# M_Driver.net
KiCad netlist of a schematic drawn in Altium Designer
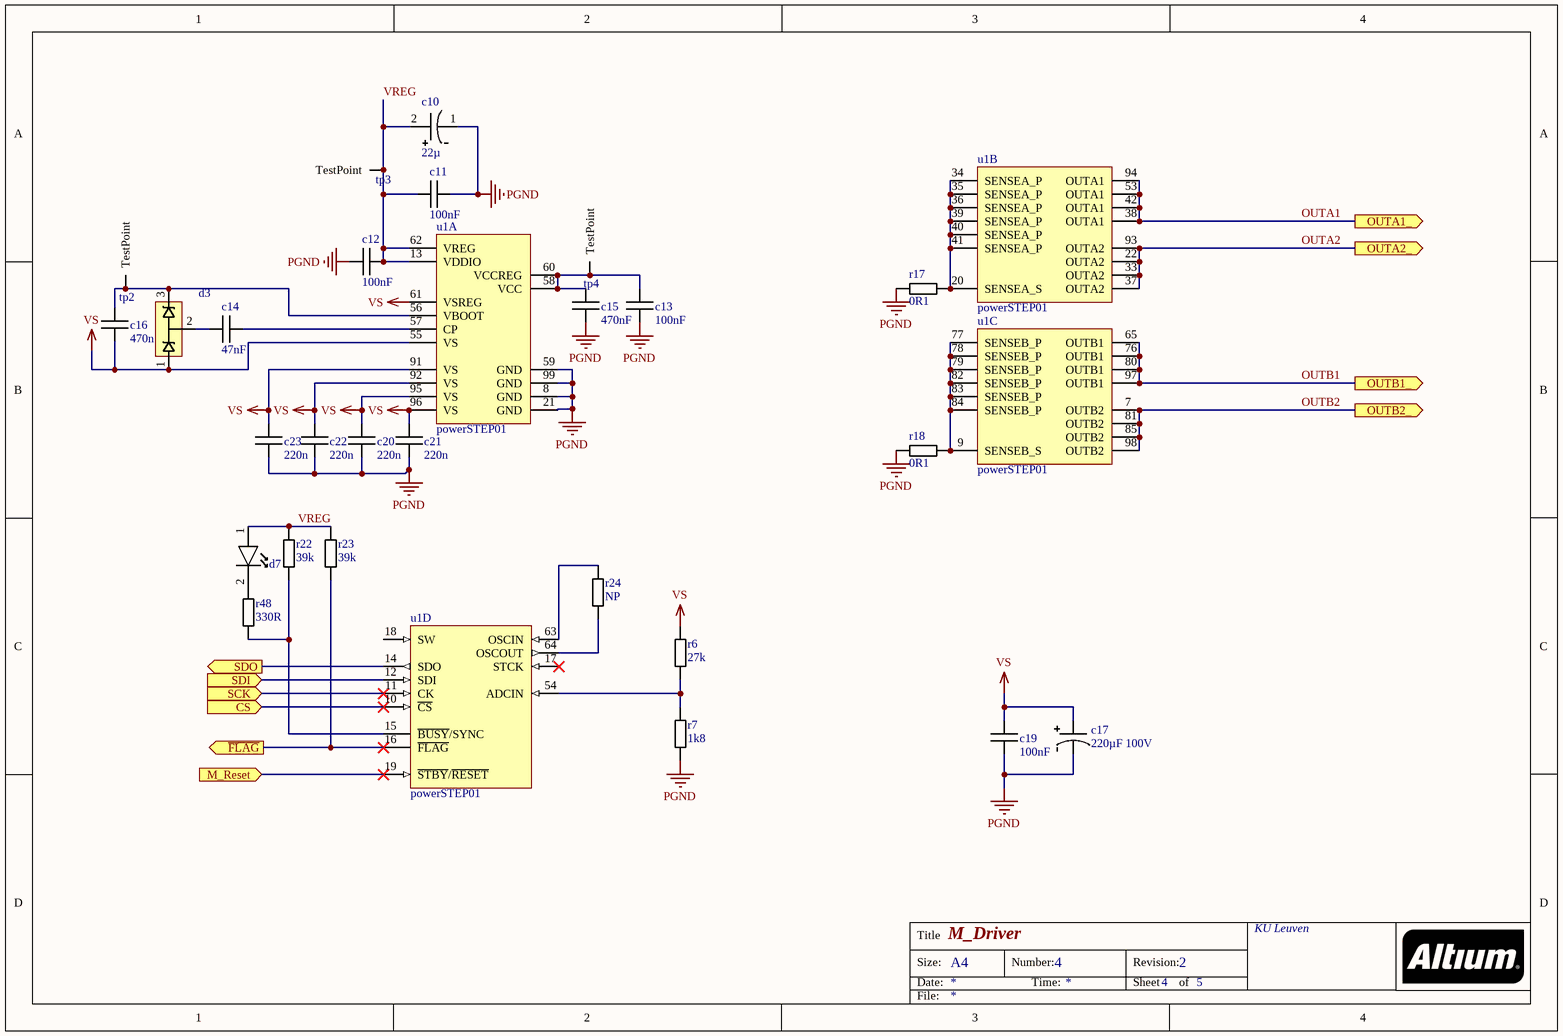
[diagram p0: M_Driver.SchDoc]

(export (version "E")
  (design (tool "Eeschema 10.0.6"))
  (components
    (comp (ref "c10") (value "22µ") (footprint "Elco-B") (libsource (lib "Panasonic") (part "Elco B")))
    (comp (ref "c11")
      (value "100nF")
      (footprint "0805")
      (description "...F")
      (libsource (lib "Generic R-C") (part "0805 Capacitor"))
    )
    (comp (ref "c12")
      (value "100nF")
      (footprint "0805")
      (description "...F")
      (libsource (lib "Generic R-C") (part "0805 Capacitor"))
    )
    (comp (ref "c13")
      (value "100nF")
      (footprint "0805")
      (description "...F")
      (libsource (lib "Generic R-C") (part "0805 Capacitor"))
    )
    (comp (ref "c14")
      (value "47nF")
      (footprint "0805")
      (description "...F")
      (libsource (lib "Generic R-C") (part "0805 Capacitor"))
    )
    (comp (ref "c15")
      (value "470nF")
      (footprint "0805")
      (description "...F")
      (libsource (lib "Generic R-C") (part "0805 Capacitor"))
    )
    (comp (ref "c16")
      (value "470n")
      (footprint "0805")
      (description "...F")
      (libsource (lib "Generic R-C") (part "0805 Capacitor"))
    )
    (comp (ref "c17")
      (value "220µF 100V")
      (footprint "TH Elco 12.5")
      (description "d = 12.5mm")
      (libsource (lib "Panasonic") (part "Elco TH d12.5"))
    )
    (comp (ref "c19")
      (value "100nF")
      (footprint "0805")
      (description "...F")
      (libsource (lib "Generic R-C") (part "0805 Capacitor"))
    )
    (comp (ref "c20")
      (value "220n")
      (footprint "0805")
      (description "...F")
      (libsource (lib "Generic R-C") (part "0805 Capacitor"))
    )
    (comp (ref "c21")
      (value "220n")
      (footprint "0805")
      (description "...F")
      (libsource (lib "Generic R-C") (part "0805 Capacitor"))
    )
    (comp (ref "c22")
      (value "220n")
      (footprint "0805")
      (description "...F")
      (libsource (lib "Generic R-C") (part "0805 Capacitor"))
    )
    (comp (ref "c23")
      (value "220n")
      (footprint "0805")
      (description "...F")
      (libsource (lib "Generic R-C") (part "0805 Capacitor"))
    )
    (comp (ref "d3") (value "BAS40-04") (footprint "SOT23") (libsource (lib "Diodes_inc") (part "BAS40-04")))
    (comp (ref "d7")
      (value "Yellow SMD LED")
      (footprint "0603 - LED")
      (description "0603 Package")
      (libsource (lib "Kingbright") (part "Yellow SMD LED"))
    )
    (comp (ref "r6")
      (value "27k")
      (footprint "0805")
      (description "...R")
      (libsource (lib "Generic R-C") (part "0805 Resistor"))
    )
    (comp (ref "r7")
      (value "1k8")
      (footprint "0805")
      (description "...R")
      (libsource (lib "Generic R-C") (part "0805 Resistor"))
    )
    (comp (ref "r17")
      (value "0R1")
      (footprint "2512")
      (description "..R")
      (libsource (lib "Generic R-C") (part "2512 Resistor"))
    )
    (comp (ref "r18")
      (value "0R1")
      (footprint "2512")
      (description "..R")
      (libsource (lib "Generic R-C") (part "2512 Resistor"))
    )
    (comp (ref "r22")
      (value "39k")
      (footprint "0805")
      (description "...R")
      (libsource (lib "Generic R-C") (part "0805 Resistor"))
    )
    (comp (ref "r23")
      (value "39k")
      (footprint "0805")
      (description "...R")
      (libsource (lib "Generic R-C") (part "0805 Resistor"))
    )
    (comp (ref "r24")
      (value "NP")
      (footprint "0603")
      (description "...R")
      (libsource (lib "Generic R-C") (part "0603 Resistor"))
    )
    (comp (ref "r48")
      (value "330R")
      (footprint "0603")
      (description "...R")
      (libsource (lib "Generic R-C") (part "0603 Resistor"))
    )
    (comp (ref "tp2")
      (value "Test Point")
      (footprint "Test Point")
      (libsource (lib "Board_Props") (part "Test Point"))
    )
    (comp (ref "tp3")
      (value "Test Point")
      (footprint "Test Point")
      (libsource (lib "Board_Props") (part "Test Point"))
    )
    (comp (ref "tp4")
      (value "Test Point")
      (footprint "Test Point")
      (libsource (lib "Board_Props") (part "Test Point"))
    )
    (comp (ref "u1")
      (value "powerSTEP01")
      (footprint "VFQFPN")
      (description "VFQFPN")
      (libsource (lib "STMicroelectronics") (part "powerSTEP01"))
    )
  )
  (nets
    (net (code "1") (name "/CS") (class "Default")
      (node (ref "u1") (pin "10") (pinfunction "~{CS}_10") (pintype "input+no_connect"))
    )
    (net (code "2") (name "/M_Reset") (class "Default")
      (node (ref "u1") (pin "19") (pinfunction "~{STBY}/~{RESET}_19") (pintype "input+no_connect"))
    )
    (net (code "3") (name "/OUTA1") (class "Default")
      (node (ref "u1") (pin "38") (pinfunction "OUTA1_38") (pintype "passive"))
      (node (ref "u1") (pin "42") (pinfunction "OUTA1_42") (pintype "passive"))
      (node (ref "u1") (pin "53") (pinfunction "OUTA1_53") (pintype "passive"))
      (node (ref "u1") (pin "94") (pinfunction "OUTA1_94") (pintype "passive"))
    )
    (net (code "4") (name "/OUTA2") (class "Default")
      (node (ref "u1") (pin "22") (pinfunction "OUTA2_22") (pintype "passive"))
      (node (ref "u1") (pin "33") (pinfunction "OUTA2_33") (pintype "passive"))
      (node (ref "u1") (pin "37") (pinfunction "OUTA2_37") (pintype "passive"))
      (node (ref "u1") (pin "93") (pinfunction "OUTA2_93") (pintype "passive"))
    )
    (net (code "5") (name "/OUTB1") (class "Default")
      (node (ref "u1") (pin "65") (pinfunction "OUTB1_65") (pintype "passive"))
      (node (ref "u1") (pin "76") (pinfunction "OUTB1_76") (pintype "passive"))
      (node (ref "u1") (pin "80") (pinfunction "OUTB1_80") (pintype "passive"))
      (node (ref "u1") (pin "97") (pinfunction "OUTB1_97") (pintype "passive"))
    )
    (net (code "6") (name "/OUTB2") (class "Default")
      (node (ref "u1") (pin "7") (pinfunction "OUTB2_7") (pintype "passive"))
      (node (ref "u1") (pin "81") (pinfunction "OUTB2_81") (pintype "passive"))
      (node (ref "u1") (pin "85") (pinfunction "OUTB2_85") (pintype "passive"))
      (node (ref "u1") (pin "98") (pinfunction "OUTB2_98") (pintype "passive"))
    )
    (net (code "7") (name "/SCK") (class "Default")
      (node (ref "u1") (pin "11") (pinfunction "CK_11") (pintype "input+no_connect"))
    )
    (net (code "8") (name "/SDI") (class "Default")
      (node (ref "u1") (pin "12") (pinfunction "SDI_12") (pintype "input"))
    )
    (net (code "9") (name "/SDO") (class "Default")
      (node (ref "u1") (pin "14") (pinfunction "SDO_14") (pintype "output"))
    )
    (net (code "10") (name "/VREG") (class "Default")
      (node (ref "c10") (pin "2") (pintype "passive"))
      (node (ref "c11") (pin "2") (pintype "passive"))
      (node (ref "c12") (pin "1") (pintype "passive"))
      (node (ref "d7") (pin "1") (pinfunction "Anode_1") (pintype "passive"))
      (node (ref "r22") (pin "1") (pintype "passive"))
      (node (ref "r23") (pin "1") (pintype "passive"))
      (node (ref "tp3") (pin "1") (pinfunction "TestPoint_1") (pintype "passive"))
      (node (ref "u1") (pin "13") (pinfunction "VDDIO_13") (pintype "power_in"))
      (node (ref "u1") (pin "62") (pinfunction "VREG_62") (pintype "power_in"))
    )
    (net (code "11") (name "/~{FLAG}") (class "Default")
      (node (ref "r23") (pin "2") (pintype "passive"))
      (node (ref "u1") (pin "16") (pinfunction "~{FLAG}_16") (pintype "open_collector"))
    )
    (net (code "12") (name "Net-(c14-Pad1)") (class "Default")
      (node (ref "c14") (pin "1") (pintype "passive"))
      (node (ref "d3") (pin "2") (pinfunction "2_2") (pintype "passive"))
    )
    (net (code "13") (name "Net-(d7-Kathode)") (class "Default")
      (node (ref "d7") (pin "2") (pinfunction "Kathode_2") (pintype "passive"))
      (node (ref "r48") (pin "2") (pintype "passive"))
    )
    (net (code "14") (name "Net-(tp2-TestPoint)") (class "Default")
      (node (ref "c16") (pin "1") (pintype "passive"))
      (node (ref "d3") (pin "3") (pinfunction "3_3") (pintype "passive"))
      (node (ref "tp2") (pin "1") (pinfunction "TestPoint_1") (pintype "passive"))
      (node (ref "u1") (pin "56") (pinfunction "VBOOT_56") (pintype "power_in"))
    )
    (net (code "15") (name "Net-(tp4-TestPoint)") (class "Default")
      (node (ref "c13") (pin "2") (pintype "passive"))
      (node (ref "c15") (pin "2") (pintype "passive"))
      (node (ref "tp4") (pin "1") (pinfunction "TestPoint_1") (pintype "passive"))
      (node (ref "u1") (pin "58") (pinfunction "VCC_58") (pintype "power_in"))
      (node (ref "u1") (pin "60") (pinfunction "VCCREG_60") (pintype "power_in"))
    )
    (net (code "16") (name "Net-(u1A-CP)") (class "Default")
      (node (ref "c14") (pin "2") (pintype "passive"))
      (node (ref "u1") (pin "57") (pinfunction "CP_57") (pintype "power_in"))
    )
    (net (code "17") (name "Net-(u1B-SENSEA_S)") (class "Default")
      (node (ref "r17") (pin "2") (pintype "passive"))
      (node (ref "u1") (pin "20") (pinfunction "SENSEA_S_20") (pintype "power_in"))
      (node (ref "u1") (pin "34") (pinfunction "SENSEA_P_34") (pintype "power_in"))
      (node (ref "u1") (pin "35") (pinfunction "SENSEA_P_35") (pintype "power_in"))
      (node (ref "u1") (pin "36") (pinfunction "SENSEA_P_36") (pintype "power_in"))
      (node (ref "u1") (pin "39") (pinfunction "SENSEA_P_39") (pintype "power_in"))
      (node (ref "u1") (pin "40") (pinfunction "SENSEA_P_40") (pintype "power_in"))
      (node (ref "u1") (pin "41") (pinfunction "SENSEA_P_41") (pintype "power_in"))
    )
    (net (code "18") (name "Net-(u1C-SENSEB_S)") (class "Default")
      (node (ref "r18") (pin "2") (pintype "passive"))
      (node (ref "u1") (pin "77") (pinfunction "SENSEB_P_77") (pintype "power_in"))
      (node (ref "u1") (pin "78") (pinfunction "SENSEB_P_78") (pintype "power_in"))
      (node (ref "u1") (pin "79") (pinfunction "SENSEB_P_79") (pintype "power_in"))
      (node (ref "u1") (pin "82") (pinfunction "SENSEB_P_82") (pintype "power_in"))
      (node (ref "u1") (pin "83") (pinfunction "SENSEB_P_83") (pintype "power_in"))
      (node (ref "u1") (pin "84") (pinfunction "SENSEB_P_84") (pintype "power_in"))
      (node (ref "u1") (pin "9") (pinfunction "SENSEB_S_9") (pintype "power_in"))
    )
    (net (code "19") (name "Net-(u1D-ADCIN)") (class "Default")
      (node (ref "r6") (pin "1") (pintype "passive"))
      (node (ref "r7") (pin "2") (pintype "passive"))
      (node (ref "u1") (pin "54") (pinfunction "ADCIN_54") (pintype "input"))
    )
    (net (code "20") (name "Net-(u1D-OSCIN)") (class "Default")
      (node (ref "r24") (pin "2") (pintype "passive"))
      (node (ref "u1") (pin "63") (pinfunction "OSCIN_63") (pintype "input"))
    )
    (net (code "21") (name "Net-(u1D-OSCOUT)") (class "Default")
      (node (ref "r24") (pin "1") (pintype "passive"))
      (node (ref "u1") (pin "64") (pinfunction "OSCOUT_64") (pintype "output"))
    )
    (net (code "22") (name "Net-(u1D-~{BUSY}{slash}SYNC)") (class "Default")
      (node (ref "r22") (pin "2") (pintype "passive"))
      (node (ref "r48") (pin "1") (pintype "passive"))
      (node (ref "u1") (pin "15") (pinfunction "~{BUSY}/SYNC_15") (pintype "open_collector"))
    )
    (net (code "23") (name "PGND") (class "Default")
      (node (ref "c10") (pin "1") (pintype "passive"))
      (node (ref "c11") (pin "1") (pintype "passive"))
      (node (ref "c12") (pin "2") (pintype "passive"))
      (node (ref "c13") (pin "1") (pintype "passive"))
      (node (ref "c15") (pin "1") (pintype "passive"))
      (node (ref "c17") (pin "1") (pintype "passive"))
      (node (ref "c19") (pin "1") (pintype "passive"))
      (node (ref "c20") (pin "2") (pintype "passive"))
      (node (ref "c21") (pin "2") (pintype "passive"))
      (node (ref "c22") (pin "2") (pintype "passive"))
      (node (ref "c23") (pin "2") (pintype "passive"))
      (node (ref "r17") (pin "1") (pintype "passive"))
      (node (ref "r18") (pin "1") (pintype "passive"))
      (node (ref "r7") (pin "1") (pintype "passive"))
      (node (ref "u1") (pin "21") (pinfunction "GND_21") (pintype "power_in"))
      (node (ref "u1") (pin "59") (pinfunction "GND_59") (pintype "power_in"))
      (node (ref "u1") (pin "8") (pinfunction "GND_8") (pintype "power_in"))
      (node (ref "u1") (pin "99") (pinfunction "GND_99") (pintype "power_in"))
    )
    (net (code "24") (name "VS") (class "Default")
      (node (ref "c16") (pin "2") (pintype "passive"))
      (node (ref "c17") (pin "2") (pintype "passive"))
      (node (ref "c19") (pin "2") (pintype "passive"))
      (node (ref "c20") (pin "1") (pintype "passive"))
      (node (ref "c21") (pin "1") (pintype "passive"))
      (node (ref "c22") (pin "1") (pintype "passive"))
      (node (ref "c23") (pin "1") (pintype "passive"))
      (node (ref "d3") (pin "1") (pinfunction "1_1") (pintype "passive"))
      (node (ref "r6") (pin "2") (pintype "passive"))
      (node (ref "u1") (pin "55") (pinfunction "VS_55") (pintype "power_in"))
      (node (ref "u1") (pin "61") (pinfunction "VSREG_61") (pintype "power_in"))
      (node (ref "u1") (pin "91") (pinfunction "VS_91") (pintype "power_in"))
      (node (ref "u1") (pin "92") (pinfunction "VS_92") (pintype "power_in"))
      (node (ref "u1") (pin "95") (pinfunction "VS_95") (pintype "power_in"))
      (node (ref "u1") (pin "96") (pinfunction "VS_96") (pintype "power_in"))
    )
    (net (code "25") (name "unconnected-(u1D-STCK-Pad17)") (class "Default")
      (node (ref "u1") (pin "17") (pinfunction "STCK_17") (pintype "input+no_connect"))
    )
    (net (code "26") (name "unconnected-(u1D-SW-Pad18)") (class "Default")
      (node (ref "u1") (pin "18") (pinfunction "SW_18") (pintype "input"))
    )
  )
)
